# pc_ads1220_brk.net
KiCad netlist of a schematic drawn in EAGLE
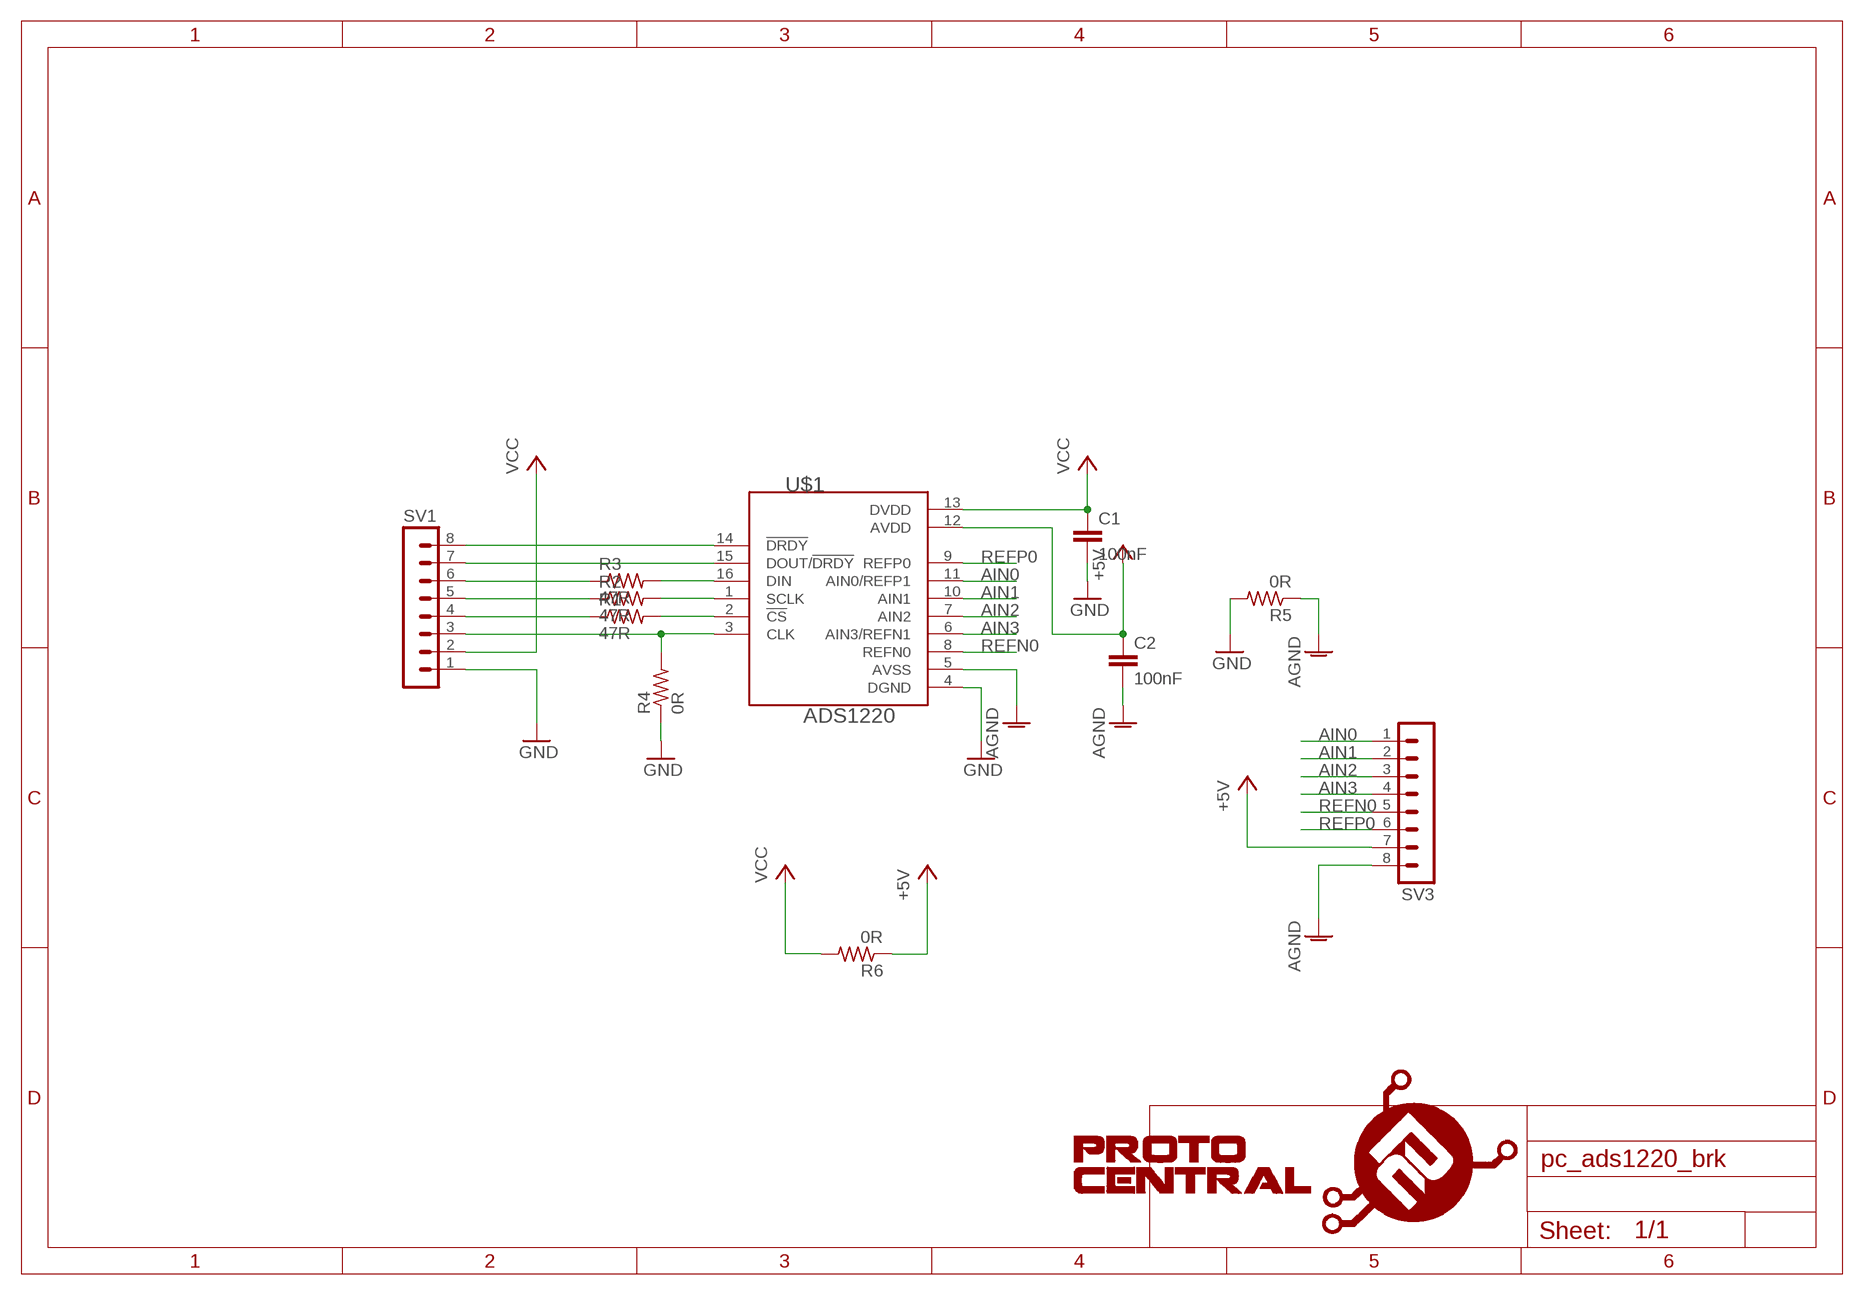
[diagram p0: schematic, sheet 1]

(export (version "E")
  (design (tool "Eeschema 10.0.6"))
  (components
    (comp (ref "C1")
      (value "100nF")
      (footprint "eagle-import:C0805")
      (libsource (lib "eagle-import") (part "C-EUC0805"))
    )
    (comp (ref "C2")
      (value "100nF")
      (footprint "eagle-import:C0805")
      (libsource (lib "eagle-import") (part "C-EUC0805"))
    )
    (comp (ref "R1")
      (value "47R")
      (footprint "eagle-import:R0805")
      (libsource (lib "eagle-import") (part "R-US_R0805"))
    )
    (comp (ref "R2")
      (value "47R")
      (footprint "eagle-import:R0805")
      (libsource (lib "eagle-import") (part "R-US_R0805"))
    )
    (comp (ref "R3")
      (value "47R")
      (footprint "eagle-import:R0805")
      (libsource (lib "eagle-import") (part "R-US_R0805"))
    )
    (comp (ref "R4")
      (value "0R")
      (footprint "eagle-import:R0805")
      (libsource (lib "eagle-import") (part "R-US_R0805"))
    )
    (comp (ref "R5")
      (value "0R")
      (footprint "eagle-import:R0805")
      (libsource (lib "eagle-import") (part "R-US_R0805"))
    )
    (comp (ref "R6")
      (value "0R")
      (footprint "eagle-import:R0805")
      (libsource (lib "eagle-import") (part "R-US_R0805"))
    )
    (comp (ref "SV1")
      (value "MA08-1")
      (footprint "eagle-import:MA08-1")
      (libsource (lib "eagle-import") (part "MA08-1"))
    )
    (comp (ref "SV3")
      (value "MA08-1")
      (footprint "eagle-import:MA08-1")
      (libsource (lib "eagle-import") (part "MA08-1"))
    )
    (comp (ref "U$1")
      (value "ADS1220")
      (footprint "eagle-import:TSSOP-16")
      (libsource (lib "eagle-import") (part "ADS1220"))
    )
    (comp (ref "U$3")
      (value "PROTY_LOGO_WITH_TEXT")
      (footprint "eagle-import:PROTY_WITH_TEXT")
      (libsource (lib "eagle-import") (part "PROTY_LOGO_WITH_TEXT"))
    )
  )
  (nets
    (net (code "1") (name "+5V") (class "Default")
      (node (ref "C2") (pin "1") (pinfunction "1_1") (pintype "passive"))
      (node (ref "R6") (pin "1") (pinfunction "1_1") (pintype "passive"))
      (node (ref "SV3") (pin "7") (pinfunction "7_7") (pintype "passive"))
      (node (ref "U$1") (pin "12") (pinfunction "AVDD_12") (pintype "bidirectional"))
    )
    (net (code "2") (name "/AIN0") (class "Default")
      (node (ref "SV3") (pin "1") (pinfunction "1_1") (pintype "passive"))
      (node (ref "U$1") (pin "11") (pinfunction "AIN0/REFP1_11") (pintype "bidirectional"))
    )
    (net (code "3") (name "/AIN1") (class "Default")
      (node (ref "SV3") (pin "2") (pinfunction "2_2") (pintype "passive"))
      (node (ref "U$1") (pin "10") (pinfunction "AIN1_10") (pintype "bidirectional"))
    )
    (net (code "4") (name "/AIN2") (class "Default")
      (node (ref "SV3") (pin "3") (pinfunction "3_3") (pintype "passive"))
      (node (ref "U$1") (pin "7") (pinfunction "AIN2_7") (pintype "bidirectional"))
    )
    (net (code "5") (name "/AIN3") (class "Default")
      (node (ref "SV3") (pin "4") (pinfunction "4_4") (pintype "passive"))
      (node (ref "U$1") (pin "6") (pinfunction "AIN3/REFN1_6") (pintype "bidirectional"))
    )
    (net (code "6") (name "/REFN0") (class "Default")
      (node (ref "SV3") (pin "5") (pinfunction "5_5") (pintype "passive"))
      (node (ref "U$1") (pin "8") (pinfunction "REFN0_8") (pintype "bidirectional"))
    )
    (net (code "7") (name "/REFP0") (class "Default")
      (node (ref "SV3") (pin "6") (pinfunction "6_6") (pintype "passive"))
      (node (ref "U$1") (pin "9") (pinfunction "REFP0_9") (pintype "bidirectional"))
    )
    (net (code "8") (name "AGND") (class "Default")
      (node (ref "C2") (pin "2") (pinfunction "2_2") (pintype "passive"))
      (node (ref "R5") (pin "1") (pinfunction "1_1") (pintype "passive"))
      (node (ref "SV3") (pin "8") (pinfunction "8_8") (pintype "passive"))
      (node (ref "U$1") (pin "5") (pinfunction "AVSS_5") (pintype "bidirectional"))
    )
    (net (code "9") (name "GND") (class "Default")
      (node (ref "C1") (pin "2") (pinfunction "2_2") (pintype "passive"))
      (node (ref "R4") (pin "1") (pinfunction "1_1") (pintype "passive"))
      (node (ref "R5") (pin "2") (pinfunction "2_2") (pintype "passive"))
      (node (ref "SV1") (pin "1") (pinfunction "1_1") (pintype "passive"))
      (node (ref "U$1") (pin "4") (pinfunction "DGND_4") (pintype "bidirectional"))
    )
    (net (code "10") (name "Net-(R1-Pad1)") (class "Default")
      (node (ref "R1") (pin "1") (pinfunction "1_1") (pintype "passive"))
      (node (ref "SV1") (pin "4") (pinfunction "4_4") (pintype "passive"))
    )
    (net (code "11") (name "Net-(R2-Pad1)") (class "Default")
      (node (ref "R2") (pin "1") (pinfunction "1_1") (pintype "passive"))
      (node (ref "SV1") (pin "5") (pinfunction "5_5") (pintype "passive"))
    )
    (net (code "12") (name "Net-(R3-Pad1)") (class "Default")
      (node (ref "R3") (pin "1") (pinfunction "1_1") (pintype "passive"))
      (node (ref "SV1") (pin "6") (pinfunction "6_6") (pintype "passive"))
    )
    (net (code "13") (name "Net-(U$1-CLK)") (class "Default")
      (node (ref "R4") (pin "2") (pinfunction "2_2") (pintype "passive"))
      (node (ref "SV1") (pin "3") (pinfunction "3_3") (pintype "passive"))
      (node (ref "U$1") (pin "3") (pinfunction "CLK_3") (pintype "bidirectional"))
    )
    (net (code "14") (name "Net-(U$1-DIN)") (class "Default")
      (node (ref "R3") (pin "2") (pinfunction "2_2") (pintype "passive"))
      (node (ref "U$1") (pin "16") (pinfunction "DIN_16") (pintype "bidirectional"))
    )
    (net (code "15") (name "Net-(U$1-DOUT{slash}~{DRDY})") (class "Default")
      (node (ref "SV1") (pin "7") (pinfunction "7_7") (pintype "passive"))
      (node (ref "U$1") (pin "15") (pinfunction "DOUT/~{DRDY}_15") (pintype "bidirectional"))
    )
    (net (code "16") (name "Net-(U$1-SCLK)") (class "Default")
      (node (ref "R2") (pin "2") (pinfunction "2_2") (pintype "passive"))
      (node (ref "U$1") (pin "1") (pinfunction "SCLK_1") (pintype "bidirectional"))
    )
    (net (code "17") (name "Net-(U$1-~{CS})") (class "Default")
      (node (ref "R1") (pin "2") (pinfunction "2_2") (pintype "passive"))
      (node (ref "U$1") (pin "2") (pinfunction "~{CS}_2") (pintype "bidirectional"))
    )
    (net (code "18") (name "Net-(U$1-~{DRDY})") (class "Default")
      (node (ref "SV1") (pin "8") (pinfunction "8_8") (pintype "passive"))
      (node (ref "U$1") (pin "14") (pinfunction "~{DRDY}_14") (pintype "bidirectional"))
    )
    (net (code "19") (name "VCC") (class "Default")
      (node (ref "C1") (pin "1") (pinfunction "1_1") (pintype "passive"))
      (node (ref "R6") (pin "2") (pinfunction "2_2") (pintype "passive"))
      (node (ref "SV1") (pin "2") (pinfunction "2_2") (pintype "passive"))
      (node (ref "U$1") (pin "13") (pinfunction "DVDD_13") (pintype "bidirectional"))
    )
  )
)
